# 01.net
KiCad netlist of a schematic drawn in EasyEDA Pro
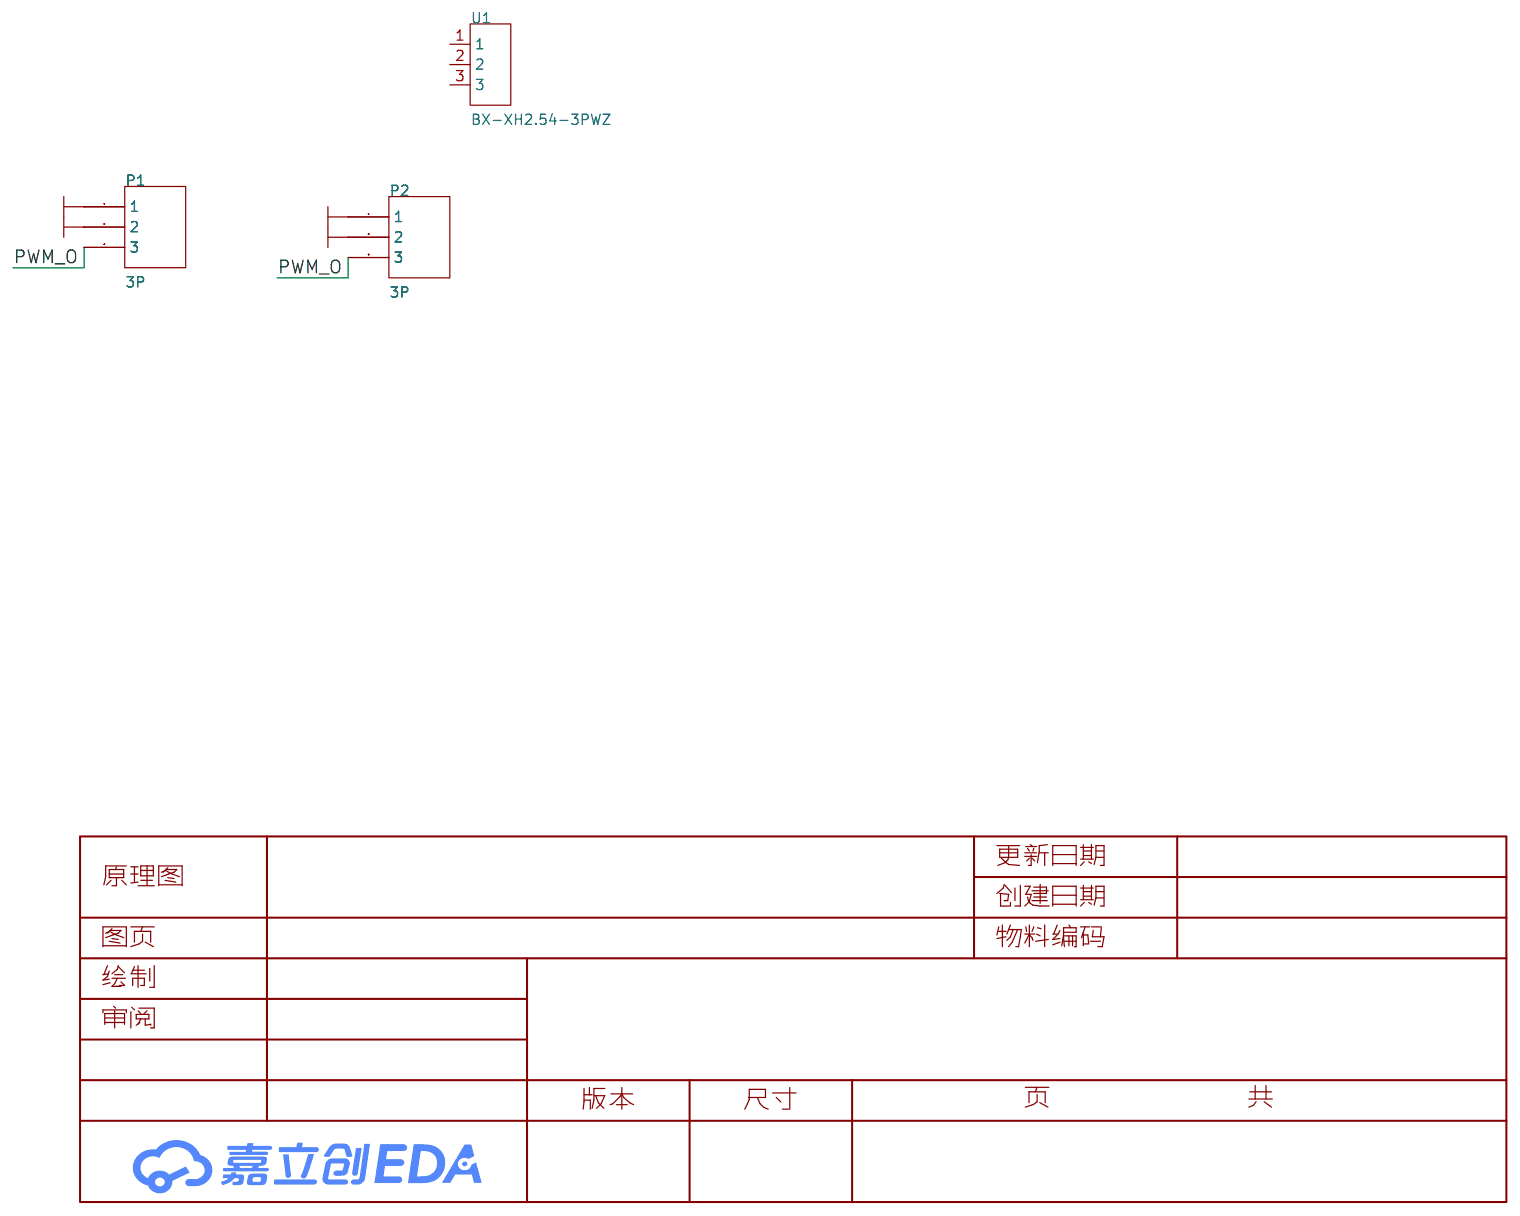
[diagram p0: schematic sheet]

(export (version "E")
  (design (tool "Eeschema 10.0.6"))
  (components
    (comp (ref "P1")
      (value "3P")
      (footprint "easyedapro:HDR1X3_P")
      (libsource (lib "easyedapro") (part "3P"))
    )
    (comp (ref "P2")
      (value "3P")
      (footprint "easyedapro:HDR1X3_P")
      (libsource (lib "easyedapro") (part "3P"))
    )
    (comp (ref "U1")
      (value "BX-XH2.54-3PWZ")
      (footprint "easyedapro:CONN-TH_3P-P2.50_BX-XH2.54-3PWZ")
      (fields (field (name "Manufacturer") "Bossie(博锡)"))
      (libsource (lib "easyedapro") (part "BX-XH2.54-3P WZ"))
    )
  )
  (nets
    (net (code "1") (name "/PWM_O") (class "Default")
      (node (ref "P1") (pin "3") (pinfunction "3_3") (pintype "unspecified"))
      (node (ref "P2") (pin "3") (pinfunction "3_3") (pintype "unspecified"))
    )
    (net (code "2") (name "24V") (class "Default")
      (node (ref "P1") (pin "1") (pinfunction "1_1") (pintype "unspecified"))
      (node (ref "P2") (pin "1") (pinfunction "1_1") (pintype "unspecified"))
    )
    (net (code "3") (name "GND") (class "Default")
      (node (ref "P1") (pin "2") (pinfunction "2_2") (pintype "unspecified"))
      (node (ref "P2") (pin "2") (pinfunction "2_2") (pintype "unspecified"))
    )
    (net (code "4") (name "unconnected-(U1-Pad1)") (class "Default")
      (node (ref "U1") (pin "1") (pinfunction "1_1") (pintype "unspecified"))
    )
    (net (code "5") (name "unconnected-(U1-Pad2)") (class "Default")
      (node (ref "U1") (pin "2") (pinfunction "2_2") (pintype "unspecified"))
    )
    (net (code "6") (name "unconnected-(U1-Pad3)") (class "Default")
      (node (ref "U1") (pin "3") (pinfunction "3_3") (pintype "unspecified"))
    )
  )
)
